# connector.net
KiCad netlist of a schematic drawn in Altium Designer
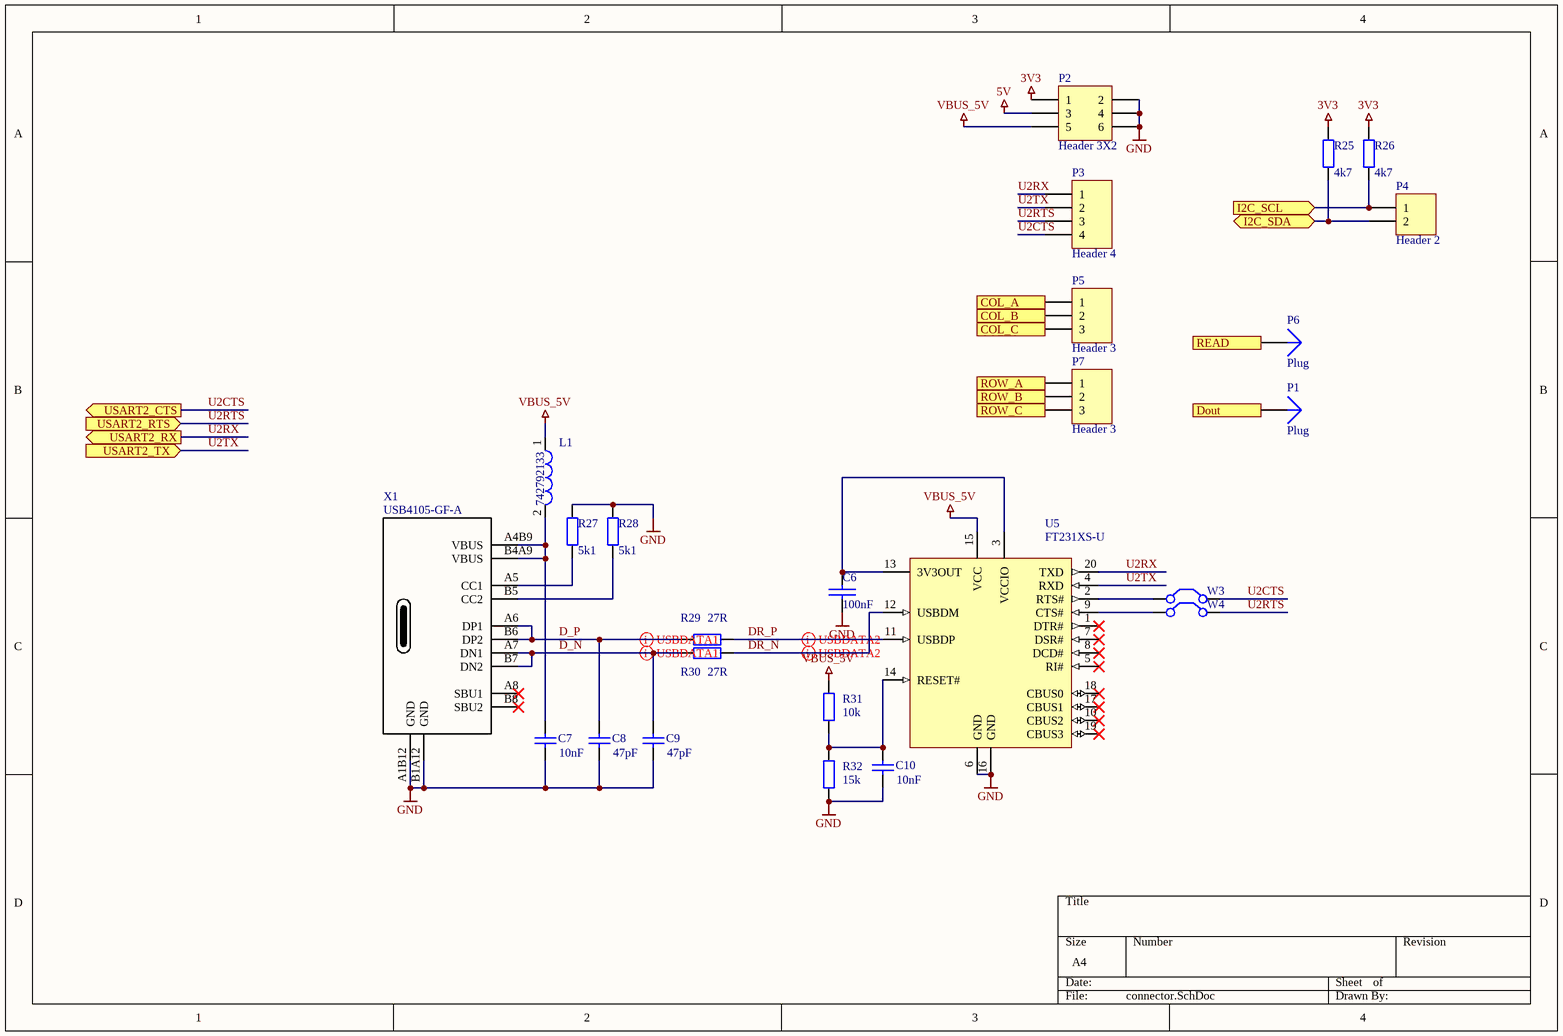
[diagram p0: connector.SchDoc]

(export (version "E")
  (design (tool "Eeschema 10.0.6"))
  (components
    (comp (ref "C6") (value "100nF") (footprint "Cap_0805") (libsource (lib "*") (part "C")))
    (comp (ref "C7")
      (value "10nF")
      (footprint "6-0805_L")
      (description "Capacitor")
      (fields (field (name "PUBLISHER") "Altium Limited"))
      (libsource (lib "Miscellaneous Devices") (part "Cap"))
    )
    (comp (ref "C8")
      (value "47pF")
      (footprint "6-0805_L")
      (description "Capacitor")
      (fields (field (name "PUBLISHER") "Altium Limited"))
      (libsource (lib "Miscellaneous Devices") (part "Cap"))
    )
    (comp (ref "C9")
      (value "47pF")
      (footprint "6-0805_L")
      (description "Capacitor")
      (fields (field (name "PUBLISHER") "Altium Limited"))
      (libsource (lib "Miscellaneous Devices") (part "Cap"))
    )
    (comp (ref "C10")
      (value "10nF")
      (footprint "Cap_0805")
      (description "Capacitor")
      (fields (field (name "PUBLISHER") "Altium Limited"))
      (libsource (lib "Miscellaneous Devices") (part "Cap"))
    )
    (comp (ref "L1")
      (value "742792133")
      (footprint "SMD-1206")
      (description "SMD EMI Suppression Ferrite Bead WE-CBF, Z = 600 Ohm")
      (libsource (lib "Altium Content Vault") (part "PAS-IND-INDUCTOR-2"))
    )
    (comp (ref "P1")
      (value "Plug")
      (footprint "PIN1")
      (fields (field (name "PUBLISHER") "Altium Limited"))
      (libsource (lib "Miscellaneous Connectors") (part "Plug"))
    )
    (comp (ref "P2")
      (value "Header 3X2")
      (footprint "HDR2X3")
      (description "Header, 3-Pin, Dual row")
      (fields (field (name "PUBLISHER") "Altium Limited"))
      (libsource (lib "Miscellaneous Connectors") (part "Header 3X2"))
    )
    (comp (ref "P3")
      (value "Header 4")
      (footprint "HDR1X4")
      (description "Header, 4-Pin")
      (fields (field (name "PUBLISHER") "Altium Limited"))
      (libsource (lib "Miscellaneous Connectors") (part "Header 4"))
    )
    (comp (ref "P4")
      (value "Header 2")
      (footprint "HDR1X2")
      (description "Header, 2-Pin")
      (fields (field (name "PUBLISHER") "Altium Limited"))
      (libsource (lib "Miscellaneous Connectors") (part "Header 2"))
    )
    (comp (ref "P5")
      (value "Header 3")
      (footprint "HDR1X3")
      (description "Header, 3-Pin")
      (fields (field (name "PUBLISHER") "Altium Limited"))
      (libsource (lib "Miscellaneous Connectors") (part "Header 3"))
    )
    (comp (ref "P6")
      (value "Plug")
      (footprint "PIN1")
      (fields (field (name "PUBLISHER") "Altium Limited"))
      (libsource (lib "Miscellaneous Connectors") (part "Plug"))
    )
    (comp (ref "P7")
      (value "Header 3")
      (footprint "HDR1X3")
      (description "Header, 3-Pin")
      (fields (field (name "PUBLISHER") "Altium Limited"))
      (libsource (lib "Miscellaneous Connectors") (part "Header 3"))
    )
    (comp (ref "R25")
      (value "4k7")
      (footprint "RES_0805")
      (description "Res 0805")
      (fields (field (name "Comment") "5k1") (field (name "PUBLISHER") "Altium Limited"))
      (libsource (lib "Miscellaneous Devices") (part "Res2"))
    )
    (comp (ref "R26")
      (value "4k7")
      (footprint "RES_0805")
      (description "Res 0805")
      (fields (field (name "Comment") "5k1") (field (name "PUBLISHER") "Altium Limited"))
      (libsource (lib "Miscellaneous Devices") (part "Res2"))
    )
    (comp (ref "R27")
      (value "5k1")
      (footprint "RES_0805")
      (description "Res 0805")
      (fields (field (name "PUBLISHER") "Altium Limited"))
      (libsource (lib "Miscellaneous Devices") (part "Res2"))
    )
    (comp (ref "R28")
      (value "5k1")
      (footprint "RES_0805")
      (description "Res 0805")
      (fields (field (name "PUBLISHER") "Altium Limited"))
      (libsource (lib "Miscellaneous Devices") (part "Res2"))
    )
    (comp (ref "R29")
      (value "27R")
      (footprint "RES_0805")
      (description "Res 0805")
      (fields (field (name "PUBLISHER") "Altium Limited"))
      (libsource (lib "") (part "Res2_1"))
    )
    (comp (ref "R30")
      (value "27R")
      (footprint "RES_0805")
      (description "Res 0805")
      (fields (field (name "PUBLISHER") "Altium Limited"))
      (libsource (lib "") (part "Res2_1"))
    )
    (comp (ref "R31")
      (value "10k")
      (footprint "RES_0805")
      (description "Res 0805")
      (fields (field (name "PUBLISHER") "Altium Limited"))
      (libsource (lib "Miscellaneous Devices") (part "Res2"))
    )
    (comp (ref "R32")
      (value "15k")
      (footprint "RES_0805")
      (description "Res 0805")
      (fields (field (name "PUBLISHER") "Altium Limited"))
      (libsource (lib "Miscellaneous Devices") (part "Res2"))
    )
    (comp (ref "U5")
      (value "FT231XS-U")
      (footprint "SSOP-20_M")
      (fields (field (name "MANUFACTURER") "FTDI"))
      (libsource (lib "Altium Content Vault") (part "COM-USB-FT231XS-IL20"))
    )
    (comp (ref "W3")
      (value "Jumper")
      (footprint "JUMPER")
      (description "Jumper Wire")
      (fields (field (name "PUBLISHER") "Altium Limited"))
      (libsource (lib "Miscellaneous Devices") (part "Jumper"))
    )
    (comp (ref "W4")
      (value "Jumper")
      (footprint "JUMPER")
      (description "Jumper Wire")
      (fields (field (name "PUBLISHER") "Altium Limited"))
      (libsource (lib "Miscellaneous Devices") (part "Jumper"))
    )
    (comp (ref "X1")
      (value "USB4105-GF-A")
      (footprint "GCT_USB4105-GF-A")
      (description "USB4105-GF-A USB connector")
      (libsource (lib "2221-LIB") (part "USB-C Type 2.0"))
    )
  )
  (nets
    (net (code "1") (name "/COL_A") (class "Default")
      (node (ref "P5") (pin "1") (pinfunction "1_1") (pintype "passive"))
    )
    (net (code "2") (name "/COL_B") (class "Default")
      (node (ref "P5") (pin "2") (pinfunction "2_2") (pintype "passive"))
    )
    (net (code "3") (name "/COL_C") (class "Default")
      (node (ref "P5") (pin "3") (pinfunction "3_3") (pintype "passive"))
    )
    (net (code "4") (name "/DR_N") (class "Default")
      (node (ref "R30") (pin "2") (pinfunction "2_2") (pintype "passive"))
      (node (ref "U5") (pin "12") (pinfunction "USBDM_12") (pintype "input"))
    )
    (net (code "5") (name "/DR_P") (class "Default")
      (node (ref "R29") (pin "2") (pinfunction "2_2") (pintype "passive"))
      (node (ref "U5") (pin "11") (pinfunction "USBDP_11") (pintype "input"))
    )
    (net (code "6") (name "/D_N") (class "Default")
      (node (ref "C9") (pin "2") (pinfunction "2_2") (pintype "passive"))
      (node (ref "R30") (pin "1") (pinfunction "1_1") (pintype "passive"))
      (node (ref "X1") (pin "A7") (pinfunction "DN1_A7") (pintype "passive"))
      (node (ref "X1") (pin "B7") (pinfunction "DN2_B7") (pintype "passive"))
    )
    (net (code "7") (name "/D_P") (class "Default")
      (node (ref "C8") (pin "2") (pinfunction "2_2") (pintype "passive"))
      (node (ref "R29") (pin "1") (pinfunction "1_1") (pintype "passive"))
      (node (ref "X1") (pin "A6") (pinfunction "DP1_A6") (pintype "passive"))
      (node (ref "X1") (pin "B6") (pinfunction "DP2_B6") (pintype "passive"))
    )
    (net (code "8") (name "/Dout") (class "Default")
      (node (ref "P1") (pin "1") (pinfunction "1_1") (pintype "passive"))
    )
    (net (code "9") (name "/I2C_SCL") (class "Default")
      (node (ref "P4") (pin "1") (pinfunction "1_1") (pintype "passive"))
      (node (ref "R26") (pin "1") (pinfunction "1_1") (pintype "passive"))
    )
    (net (code "10") (name "/I2C_SDA") (class "Default")
      (node (ref "P4") (pin "2") (pinfunction "2_2") (pintype "passive"))
      (node (ref "R25") (pin "1") (pinfunction "1_1") (pintype "passive"))
    )
    (net (code "11") (name "/READ") (class "Default")
      (node (ref "P6") (pin "1") (pinfunction "1_1") (pintype "passive"))
    )
    (net (code "12") (name "/ROW_A") (class "Default")
      (node (ref "P7") (pin "1") (pinfunction "1_1") (pintype "passive"))
    )
    (net (code "13") (name "/ROW_B") (class "Default")
      (node (ref "P7") (pin "2") (pinfunction "2_2") (pintype "passive"))
    )
    (net (code "14") (name "/ROW_C") (class "Default")
      (node (ref "P7") (pin "3") (pinfunction "3_3") (pintype "passive"))
    )
    (net (code "15") (name "/U2CTS") (class "Default")
      (node (ref "P3") (pin "4") (pinfunction "4_4") (pintype "passive"))
      (node (ref "W3") (pin "2") (pinfunction "C2_2") (pintype "passive"))
    )
    (net (code "16") (name "/U2RTS") (class "Default")
      (node (ref "P3") (pin "3") (pinfunction "3_3") (pintype "passive"))
      (node (ref "W4") (pin "2") (pinfunction "C2_2") (pintype "passive"))
    )
    (net (code "17") (name "/U2RX") (class "Default")
      (node (ref "P3") (pin "1") (pinfunction "1_1") (pintype "passive"))
      (node (ref "U5") (pin "20") (pinfunction "TXD_20") (pintype "output"))
    )
    (net (code "18") (name "/U2TX") (class "Default")
      (node (ref "P3") (pin "2") (pinfunction "2_2") (pintype "passive"))
      (node (ref "U5") (pin "4") (pinfunction "RXD_4") (pintype "input"))
    )
    (net (code "19") (name "3V3") (class "Default")
      (node (ref "P2") (pin "1") (pinfunction "1_1") (pintype "passive"))
      (node (ref "R25") (pin "2") (pinfunction "2_2") (pintype "passive"))
      (node (ref "R26") (pin "2") (pinfunction "2_2") (pintype "passive"))
    )
    (net (code "20") (name "5V") (class "Default")
      (node (ref "P2") (pin "3") (pinfunction "3_3") (pintype "passive"))
    )
    (net (code "21") (name "GND") (class "Default")
      (node (ref "C10") (pin "1") (pinfunction "1_1") (pintype "passive"))
      (node (ref "C6") (pin "2") (pinfunction "2_2") (pintype "passive"))
      (node (ref "C7") (pin "1") (pinfunction "1_1") (pintype "passive"))
      (node (ref "C8") (pin "1") (pinfunction "1_1") (pintype "passive"))
      (node (ref "C9") (pin "1") (pinfunction "1_1") (pintype "passive"))
      (node (ref "P2") (pin "2") (pinfunction "2_2") (pintype "passive"))
      (node (ref "P2") (pin "4") (pinfunction "4_4") (pintype "passive"))
      (node (ref "P2") (pin "6") (pinfunction "6_6") (pintype "passive"))
      (node (ref "R27") (pin "2") (pinfunction "2_2") (pintype "passive"))
      (node (ref "R28") (pin "2") (pinfunction "2_2") (pintype "passive"))
      (node (ref "R32") (pin "1") (pinfunction "1_1") (pintype "passive"))
      (node (ref "U5") (pin "16") (pinfunction "GND_16") (pintype "power_in"))
      (node (ref "U5") (pin "6") (pinfunction "GND_6") (pintype "power_in"))
      (node (ref "X1") (pin "A1B12") (pinfunction "GND_A1B12") (pintype "passive"))
      (node (ref "X1") (pin "B1A12") (pinfunction "GND_B1A12") (pintype "passive"))
    )
    (net (code "22") (name "Net-(C7-Pad2)") (class "Default")
      (node (ref "C7") (pin "2") (pinfunction "2_2") (pintype "passive"))
      (node (ref "L1") (pin "2") (pinfunction "2_2") (pintype "passive"))
      (node (ref "X1") (pin "A4B9") (pinfunction "VBUS_A4B9") (pintype "passive"))
      (node (ref "X1") (pin "B4A9") (pinfunction "VBUS_B4A9") (pintype "passive"))
    )
    (net (code "23") (name "Net-(U5-3V3OUT)") (class "Default")
      (node (ref "C6") (pin "1") (pinfunction "1_1") (pintype "passive"))
      (node (ref "U5") (pin "13") (pinfunction "3V3OUT_13") (pintype "power_in"))
      (node (ref "U5") (pin "3") (pinfunction "VCCIO_3") (pintype "power_in"))
    )
    (net (code "24") (name "Net-(U5-CTS#)") (class "Default")
      (node (ref "U5") (pin "9") (pinfunction "CTS#_9") (pintype "input"))
      (node (ref "W4") (pin "1") (pinfunction "C1_1") (pintype "passive"))
    )
    (net (code "25") (name "Net-(U5-RESET#)") (class "Default")
      (node (ref "C10") (pin "2") (pinfunction "2_2") (pintype "passive"))
      (node (ref "R31") (pin "1") (pinfunction "1_1") (pintype "passive"))
      (node (ref "R32") (pin "2") (pinfunction "2_2") (pintype "passive"))
      (node (ref "U5") (pin "14") (pinfunction "RESET#_14") (pintype "input"))
    )
    (net (code "26") (name "Net-(U5-RTS#)") (class "Default")
      (node (ref "U5") (pin "2") (pinfunction "RTS#_2") (pintype "output"))
      (node (ref "W3") (pin "1") (pinfunction "C1_1") (pintype "passive"))
    )
    (net (code "27") (name "Net-(X1-CC1)") (class "Default")
      (node (ref "R27") (pin "1") (pinfunction "1_1") (pintype "passive"))
      (node (ref "X1") (pin "A5") (pinfunction "CC1_A5") (pintype "passive"))
    )
    (net (code "28") (name "Net-(X1-CC2)") (class "Default")
      (node (ref "R28") (pin "1") (pinfunction "1_1") (pintype "passive"))
      (node (ref "X1") (pin "B5") (pinfunction "CC2_B5") (pintype "passive"))
    )
    (net (code "29") (name "VBUS_5V") (class "Default")
      (node (ref "L1") (pin "1") (pinfunction "1_1") (pintype "passive"))
      (node (ref "P2") (pin "5") (pinfunction "5_5") (pintype "passive"))
      (node (ref "R31") (pin "2") (pinfunction "2_2") (pintype "passive"))
      (node (ref "U5") (pin "15") (pinfunction "VCC_15") (pintype "power_in"))
    )
    (net (code "30") (name "unconnected-(U5-CBUS0-Pad18)") (class "Default")
      (node (ref "U5") (pin "18") (pinfunction "CBUS0_18") (pintype "bidirectional+no_connect"))
    )
    (net (code "31") (name "unconnected-(U5-CBUS1-Pad17)") (class "Default")
      (node (ref "U5") (pin "17") (pinfunction "CBUS1_17") (pintype "bidirectional+no_connect"))
    )
    (net (code "32") (name "unconnected-(U5-CBUS2-Pad10)") (class "Default")
      (node (ref "U5") (pin "10") (pinfunction "CBUS2_10") (pintype "bidirectional+no_connect"))
    )
    (net (code "33") (name "unconnected-(U5-CBUS3-Pad19)") (class "Default")
      (node (ref "U5") (pin "19") (pinfunction "CBUS3_19") (pintype "bidirectional+no_connect"))
    )
    (net (code "34") (name "unconnected-(U5-DCD#-Pad8)") (class "Default")
      (node (ref "U5") (pin "8") (pinfunction "DCD#_8") (pintype "input+no_connect"))
    )
    (net (code "35") (name "unconnected-(U5-DSR#-Pad7)") (class "Default")
      (node (ref "U5") (pin "7") (pinfunction "DSR#_7") (pintype "input+no_connect"))
    )
    (net (code "36") (name "unconnected-(U5-DTR#-Pad1)") (class "Default")
      (node (ref "U5") (pin "1") (pinfunction "DTR#_1") (pintype "output+no_connect"))
    )
    (net (code "37") (name "unconnected-(U5-RI#-Pad5)") (class "Default")
      (node (ref "U5") (pin "5") (pinfunction "RI#_5") (pintype "input+no_connect"))
    )
    (net (code "38") (name "unconnected-(X1-SBU1-PadA8)") (class "Default")
      (node (ref "X1") (pin "A8") (pinfunction "SBU1_A8") (pintype "passive+no_connect"))
    )
    (net (code "39") (name "unconnected-(X1-SBU2-PadB8)") (class "Default")
      (node (ref "X1") (pin "B8") (pinfunction "SBU2_B8") (pintype "passive+no_connect"))
    )
  )
)
